# Arduino_Keyboard.net
KiCad netlist of a schematic drawn in EAGLE
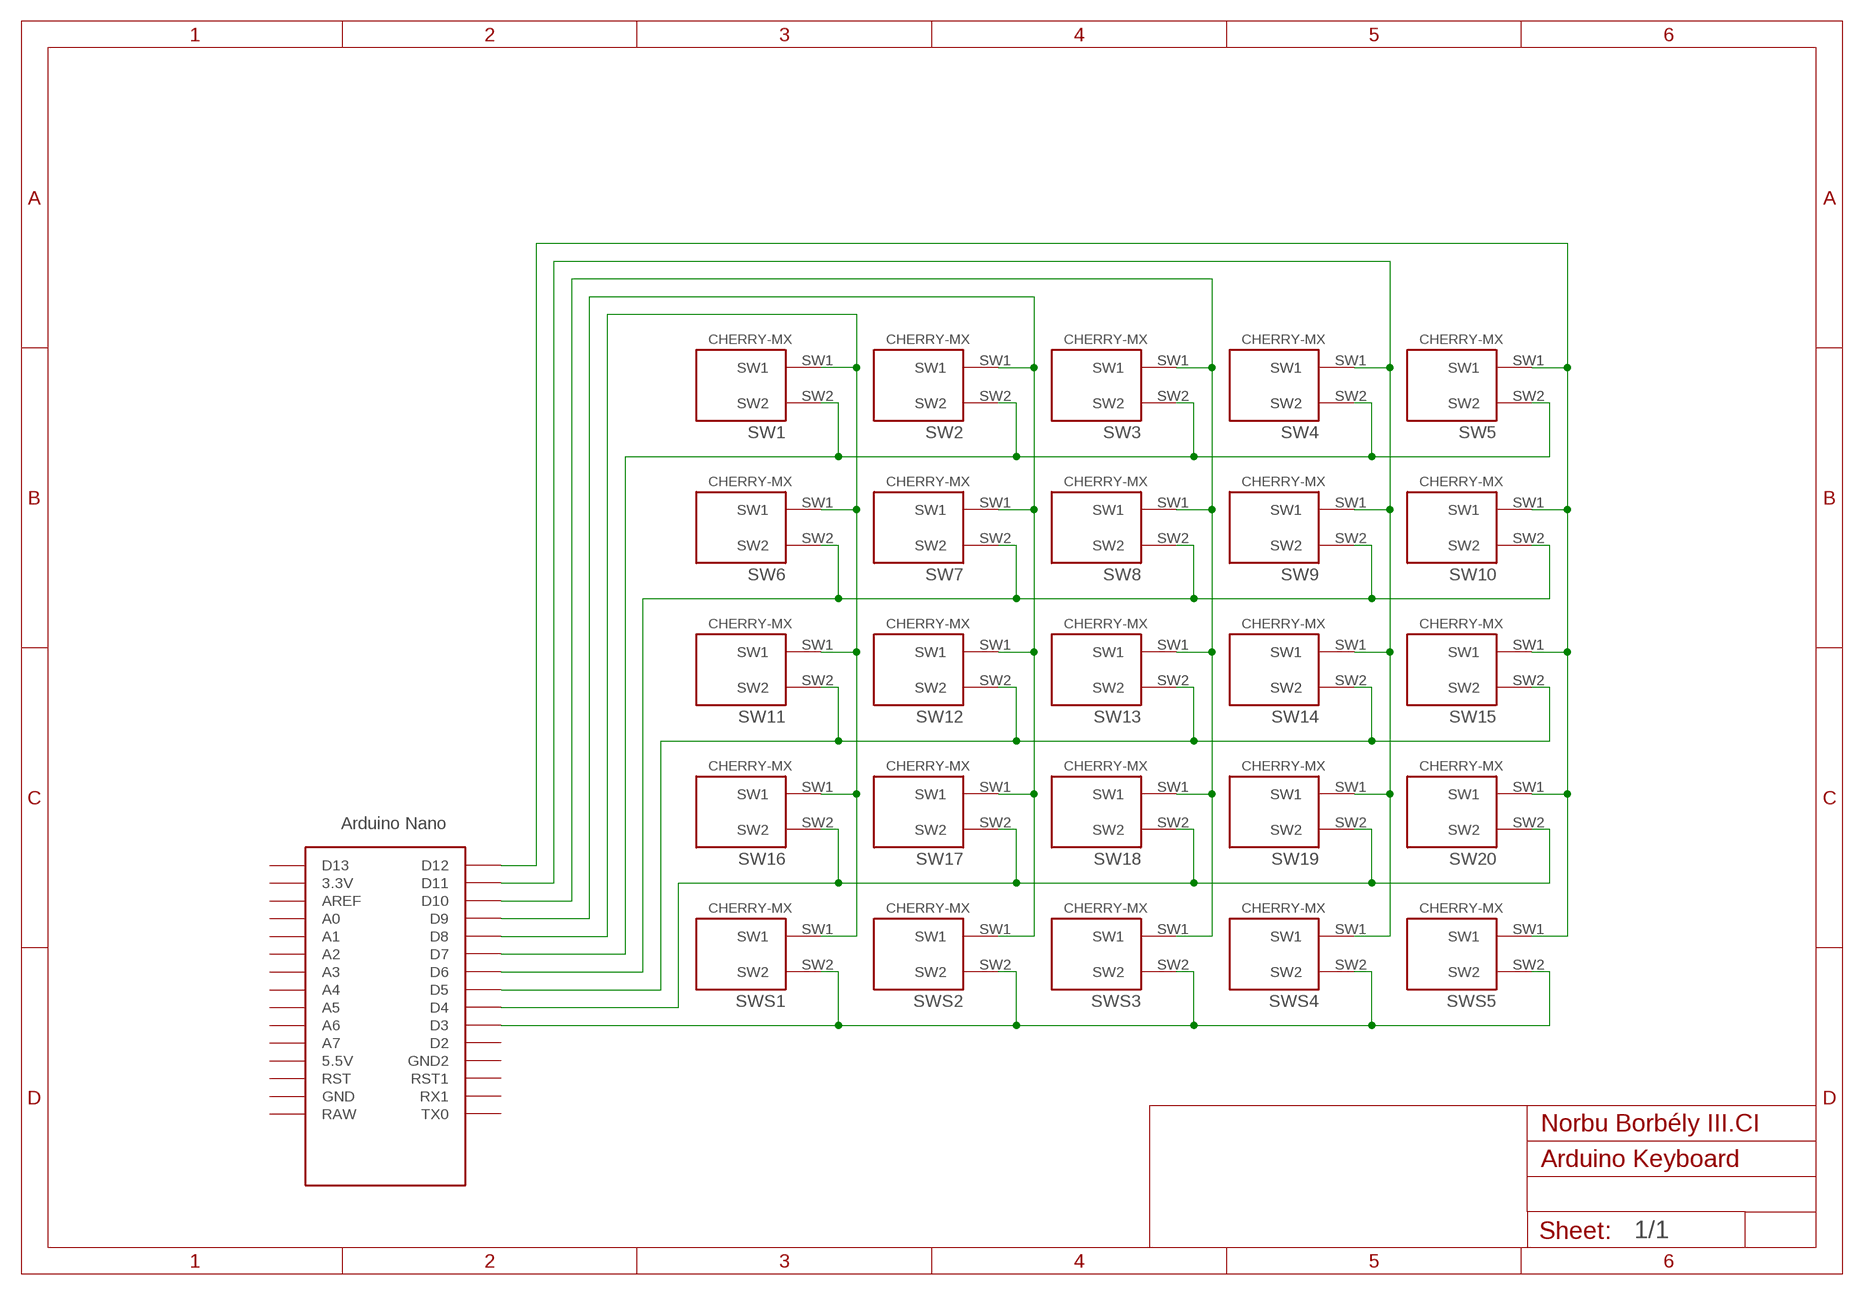
[diagram p0: schematic, sheet 1]

(export (version "E")
  (design (tool "Eeschema 10.0.6"))
  (components
    (comp (ref "SW1")
      (value "CHERRY-MXSTANDARD")
      (footprint "eagle-import:CHERRY-MX")
      (libsource (lib "eagle-import") (part "CHERRY-MXSTANDARD"))
    )
    (comp (ref "SW2")
      (value "CHERRY-MXSTANDARD")
      (footprint "eagle-import:CHERRY-MX")
      (libsource (lib "eagle-import") (part "CHERRY-MXSTANDARD"))
    )
    (comp (ref "SW3")
      (value "CHERRY-MXSTANDARD")
      (footprint "eagle-import:CHERRY-MX")
      (libsource (lib "eagle-import") (part "CHERRY-MXSTANDARD"))
    )
    (comp (ref "SW4")
      (value "CHERRY-MXSTANDARD")
      (footprint "eagle-import:CHERRY-MX")
      (libsource (lib "eagle-import") (part "CHERRY-MXSTANDARD"))
    )
    (comp (ref "SW5")
      (value "CHERRY-MXSTANDARD")
      (footprint "eagle-import:CHERRY-MX")
      (libsource (lib "eagle-import") (part "CHERRY-MXSTANDARD"))
    )
    (comp (ref "SW6")
      (value "CHERRY-MXSTANDARD")
      (footprint "eagle-import:CHERRY-MX")
      (libsource (lib "eagle-import") (part "CHERRY-MXSTANDARD"))
    )
    (comp (ref "SW7")
      (value "CHERRY-MXSTANDARD")
      (footprint "eagle-import:CHERRY-MX")
      (libsource (lib "eagle-import") (part "CHERRY-MXSTANDARD"))
    )
    (comp (ref "SW8")
      (value "CHERRY-MXSTANDARD")
      (footprint "eagle-import:CHERRY-MX")
      (libsource (lib "eagle-import") (part "CHERRY-MXSTANDARD"))
    )
    (comp (ref "SW9")
      (value "CHERRY-MXSTANDARD")
      (footprint "eagle-import:CHERRY-MX")
      (libsource (lib "eagle-import") (part "CHERRY-MXSTANDARD"))
    )
    (comp (ref "SW10")
      (value "CHERRY-MXSTANDARD")
      (footprint "eagle-import:CHERRY-MX")
      (libsource (lib "eagle-import") (part "CHERRY-MXSTANDARD"))
    )
    (comp (ref "SW11")
      (value "CHERRY-MXSTANDARD")
      (footprint "eagle-import:CHERRY-MX")
      (libsource (lib "eagle-import") (part "CHERRY-MXSTANDARD"))
    )
    (comp (ref "SW12")
      (value "CHERRY-MXSTANDARD")
      (footprint "eagle-import:CHERRY-MX")
      (libsource (lib "eagle-import") (part "CHERRY-MXSTANDARD"))
    )
    (comp (ref "SW13")
      (value "CHERRY-MXSTANDARD")
      (footprint "eagle-import:CHERRY-MX")
      (libsource (lib "eagle-import") (part "CHERRY-MXSTANDARD"))
    )
    (comp (ref "SW14")
      (value "CHERRY-MXSTANDARD")
      (footprint "eagle-import:CHERRY-MX")
      (libsource (lib "eagle-import") (part "CHERRY-MXSTANDARD"))
    )
    (comp (ref "SW15")
      (value "CHERRY-MXSTANDARD")
      (footprint "eagle-import:CHERRY-MX")
      (libsource (lib "eagle-import") (part "CHERRY-MXSTANDARD"))
    )
    (comp (ref "SW16")
      (value "CHERRY-MXSTANDARD")
      (footprint "eagle-import:CHERRY-MX")
      (libsource (lib "eagle-import") (part "CHERRY-MXSTANDARD"))
    )
    (comp (ref "SW17")
      (value "CHERRY-MXSTANDARD")
      (footprint "eagle-import:CHERRY-MX")
      (libsource (lib "eagle-import") (part "CHERRY-MXSTANDARD"))
    )
    (comp (ref "SW18")
      (value "CHERRY-MXSTANDARD")
      (footprint "eagle-import:CHERRY-MX")
      (libsource (lib "eagle-import") (part "CHERRY-MXSTANDARD"))
    )
    (comp (ref "SW19")
      (value "CHERRY-MXSTANDARD")
      (footprint "eagle-import:CHERRY-MX")
      (libsource (lib "eagle-import") (part "CHERRY-MXSTANDARD"))
    )
    (comp (ref "SW20")
      (value "CHERRY-MXSTANDARD")
      (footprint "eagle-import:CHERRY-MX")
      (libsource (lib "eagle-import") (part "CHERRY-MXSTANDARD"))
    )
    (comp (ref "SWS1")
      (value "CHERRY-MXSTANDARD")
      (footprint "eagle-import:CHERRY-MX")
      (libsource (lib "eagle-import") (part "CHERRY-MXSTANDARD"))
    )
    (comp (ref "SWS2")
      (value "CHERRY-MXSTANDARD")
      (footprint "eagle-import:CHERRY-MX")
      (libsource (lib "eagle-import") (part "CHERRY-MXSTANDARD"))
    )
    (comp (ref "SWS3")
      (value "CHERRY-MXSTANDARD")
      (footprint "eagle-import:CHERRY-MX")
      (libsource (lib "eagle-import") (part "CHERRY-MXSTANDARD"))
    )
    (comp (ref "SWS4")
      (value "CHERRY-MXSTANDARD")
      (footprint "eagle-import:CHERRY-MX")
      (libsource (lib "eagle-import") (part "CHERRY-MXSTANDARD"))
    )
    (comp (ref "SWS5")
      (value "CHERRY-MXSTANDARD")
      (footprint "eagle-import:CHERRY-MX")
      (libsource (lib "eagle-import") (part "CHERRY-MXSTANDARD"))
    )
    (comp (ref "U$1")
      (value "NANO")
      (footprint "eagle-import:NANO")
      (libsource (lib "eagle-import") (part "NANO"))
    )
  )
  (nets
    (net (code "1") (name "Net-(SW1-PadSW1)") (class "Default")
      (node (ref "SW1") (pin "SW1") (pinfunction "SW1_SW1") (pintype "bidirectional"))
      (node (ref "SW11") (pin "SW1") (pinfunction "SW1_SW1") (pintype "bidirectional"))
      (node (ref "SW16") (pin "SW1") (pinfunction "SW1_SW1") (pintype "bidirectional"))
      (node (ref "SW6") (pin "SW1") (pinfunction "SW1_SW1") (pintype "bidirectional"))
      (node (ref "SWS1") (pin "SW1") (pinfunction "SW1_SW1") (pintype "bidirectional"))
      (node (ref "U$1") (pin "D8") (pinfunction "D8_D8") (pintype "bidirectional"))
    )
    (net (code "2") (name "Net-(SW1-PadSW2)") (class "Default")
      (node (ref "SW1") (pin "SW2") (pinfunction "SW2_SW2") (pintype "bidirectional"))
      (node (ref "SW2") (pin "SW2") (pinfunction "SW2_SW2") (pintype "bidirectional"))
      (node (ref "SW3") (pin "SW2") (pinfunction "SW2_SW2") (pintype "bidirectional"))
      (node (ref "SW4") (pin "SW2") (pinfunction "SW2_SW2") (pintype "bidirectional"))
      (node (ref "SW5") (pin "SW2") (pinfunction "SW2_SW2") (pintype "bidirectional"))
      (node (ref "U$1") (pin "D7") (pinfunction "D7_D7") (pintype "bidirectional"))
    )
    (net (code "3") (name "Net-(SW10-PadSW1)") (class "Default")
      (node (ref "SW10") (pin "SW1") (pinfunction "SW1_SW1") (pintype "bidirectional"))
      (node (ref "SW15") (pin "SW1") (pinfunction "SW1_SW1") (pintype "bidirectional"))
      (node (ref "SW20") (pin "SW1") (pinfunction "SW1_SW1") (pintype "bidirectional"))
      (node (ref "SW5") (pin "SW1") (pinfunction "SW1_SW1") (pintype "bidirectional"))
      (node (ref "SWS5") (pin "SW1") (pinfunction "SW1_SW1") (pintype "bidirectional"))
      (node (ref "U$1") (pin "D12") (pinfunction "D12_D12") (pintype "bidirectional"))
    )
    (net (code "4") (name "Net-(SW10-PadSW2)") (class "Default")
      (node (ref "SW10") (pin "SW2") (pinfunction "SW2_SW2") (pintype "bidirectional"))
      (node (ref "SW6") (pin "SW2") (pinfunction "SW2_SW2") (pintype "bidirectional"))
      (node (ref "SW7") (pin "SW2") (pinfunction "SW2_SW2") (pintype "bidirectional"))
      (node (ref "SW8") (pin "SW2") (pinfunction "SW2_SW2") (pintype "bidirectional"))
      (node (ref "SW9") (pin "SW2") (pinfunction "SW2_SW2") (pintype "bidirectional"))
      (node (ref "U$1") (pin "D6") (pinfunction "D6_D6") (pintype "bidirectional"))
    )
    (net (code "5") (name "Net-(SW11-PadSW2)") (class "Default")
      (node (ref "SW11") (pin "SW2") (pinfunction "SW2_SW2") (pintype "bidirectional"))
      (node (ref "SW12") (pin "SW2") (pinfunction "SW2_SW2") (pintype "bidirectional"))
      (node (ref "SW13") (pin "SW2") (pinfunction "SW2_SW2") (pintype "bidirectional"))
      (node (ref "SW14") (pin "SW2") (pinfunction "SW2_SW2") (pintype "bidirectional"))
      (node (ref "SW15") (pin "SW2") (pinfunction "SW2_SW2") (pintype "bidirectional"))
      (node (ref "U$1") (pin "D5") (pinfunction "D5_D5") (pintype "bidirectional"))
    )
    (net (code "6") (name "Net-(SW12-PadSW1)") (class "Default")
      (node (ref "SW12") (pin "SW1") (pinfunction "SW1_SW1") (pintype "bidirectional"))
      (node (ref "SW17") (pin "SW1") (pinfunction "SW1_SW1") (pintype "bidirectional"))
      (node (ref "SW2") (pin "SW1") (pinfunction "SW1_SW1") (pintype "bidirectional"))
      (node (ref "SW7") (pin "SW1") (pinfunction "SW1_SW1") (pintype "bidirectional"))
      (node (ref "SWS2") (pin "SW1") (pinfunction "SW1_SW1") (pintype "bidirectional"))
      (node (ref "U$1") (pin "D9") (pinfunction "D9_D9") (pintype "bidirectional"))
    )
    (net (code "7") (name "Net-(SW13-PadSW1)") (class "Default")
      (node (ref "SW13") (pin "SW1") (pinfunction "SW1_SW1") (pintype "bidirectional"))
      (node (ref "SW18") (pin "SW1") (pinfunction "SW1_SW1") (pintype "bidirectional"))
      (node (ref "SW3") (pin "SW1") (pinfunction "SW1_SW1") (pintype "bidirectional"))
      (node (ref "SW8") (pin "SW1") (pinfunction "SW1_SW1") (pintype "bidirectional"))
      (node (ref "SWS3") (pin "SW1") (pinfunction "SW1_SW1") (pintype "bidirectional"))
      (node (ref "U$1") (pin "D10") (pinfunction "D10_D10") (pintype "bidirectional"))
    )
    (net (code "8") (name "Net-(SW14-PadSW1)") (class "Default")
      (node (ref "SW14") (pin "SW1") (pinfunction "SW1_SW1") (pintype "bidirectional"))
      (node (ref "SW19") (pin "SW1") (pinfunction "SW1_SW1") (pintype "bidirectional"))
      (node (ref "SW4") (pin "SW1") (pinfunction "SW1_SW1") (pintype "bidirectional"))
      (node (ref "SW9") (pin "SW1") (pinfunction "SW1_SW1") (pintype "bidirectional"))
      (node (ref "SWS4") (pin "SW1") (pinfunction "SW1_SW1") (pintype "bidirectional"))
      (node (ref "U$1") (pin "D11") (pinfunction "D11_D11") (pintype "bidirectional"))
    )
    (net (code "9") (name "Net-(SW16-PadSW2)") (class "Default")
      (node (ref "SW16") (pin "SW2") (pinfunction "SW2_SW2") (pintype "bidirectional"))
      (node (ref "SW17") (pin "SW2") (pinfunction "SW2_SW2") (pintype "bidirectional"))
      (node (ref "SW18") (pin "SW2") (pinfunction "SW2_SW2") (pintype "bidirectional"))
      (node (ref "SW19") (pin "SW2") (pinfunction "SW2_SW2") (pintype "bidirectional"))
      (node (ref "SW20") (pin "SW2") (pinfunction "SW2_SW2") (pintype "bidirectional"))
      (node (ref "U$1") (pin "D4") (pinfunction "D4_D4") (pintype "bidirectional"))
    )
    (net (code "10") (name "Net-(SWS1-PadSW2)") (class "Default")
      (node (ref "SWS1") (pin "SW2") (pinfunction "SW2_SW2") (pintype "bidirectional"))
      (node (ref "SWS2") (pin "SW2") (pinfunction "SW2_SW2") (pintype "bidirectional"))
      (node (ref "SWS3") (pin "SW2") (pinfunction "SW2_SW2") (pintype "bidirectional"))
      (node (ref "SWS4") (pin "SW2") (pinfunction "SW2_SW2") (pintype "bidirectional"))
      (node (ref "SWS5") (pin "SW2") (pinfunction "SW2_SW2") (pintype "bidirectional"))
      (node (ref "U$1") (pin "D3") (pinfunction "D3_D3") (pintype "bidirectional"))
    )
    (net (code "11") (name "unconnected-(U$1-5.5V-Pad5V)") (class "Default")
      (node (ref "U$1") (pin "5V") (pinfunction "5.5V_5V") (pintype "bidirectional"))
    )
    (net (code "12") (name "unconnected-(U$1-GND2-PadGND1)") (class "Default")
      (node (ref "U$1") (pin "GND1") (pinfunction "GND2_GND1") (pintype "bidirectional"))
    )
    (net (code "13") (name "unconnected-(U$1-Pad3.3V)") (class "Default")
      (node (ref "U$1") (pin "3.3V") (pinfunction "3.3V_3.3V") (pintype "bidirectional"))
    )
    (net (code "14") (name "unconnected-(U$1-PadA0)") (class "Default")
      (node (ref "U$1") (pin "A0") (pinfunction "A0_A0") (pintype "bidirectional"))
    )
    (net (code "15") (name "unconnected-(U$1-PadA1)") (class "Default")
      (node (ref "U$1") (pin "A1") (pinfunction "A1_A1") (pintype "bidirectional"))
    )
    (net (code "16") (name "unconnected-(U$1-PadA2)") (class "Default")
      (node (ref "U$1") (pin "A2") (pinfunction "A2_A2") (pintype "bidirectional"))
    )
    (net (code "17") (name "unconnected-(U$1-PadA3)") (class "Default")
      (node (ref "U$1") (pin "A3") (pinfunction "A3_A3") (pintype "bidirectional"))
    )
    (net (code "18") (name "unconnected-(U$1-PadA4)") (class "Default")
      (node (ref "U$1") (pin "A4") (pinfunction "A4_A4") (pintype "bidirectional"))
    )
    (net (code "19") (name "unconnected-(U$1-PadA5)") (class "Default")
      (node (ref "U$1") (pin "A5") (pinfunction "A5_A5") (pintype "bidirectional"))
    )
    (net (code "20") (name "unconnected-(U$1-PadA6)") (class "Default")
      (node (ref "U$1") (pin "A6") (pinfunction "A6_A6") (pintype "bidirectional"))
    )
    (net (code "21") (name "unconnected-(U$1-PadA7)") (class "Default")
      (node (ref "U$1") (pin "A7") (pinfunction "A7_A7") (pintype "bidirectional"))
    )
    (net (code "22") (name "unconnected-(U$1-PadAREF)") (class "Default")
      (node (ref "U$1") (pin "AREF") (pinfunction "AREF_AREF") (pintype "bidirectional"))
    )
    (net (code "23") (name "unconnected-(U$1-PadD2)") (class "Default")
      (node (ref "U$1") (pin "D2") (pinfunction "D2_D2") (pintype "bidirectional"))
    )
    (net (code "24") (name "unconnected-(U$1-PadD13)") (class "Default")
      (node (ref "U$1") (pin "D13") (pinfunction "D13_D13") (pintype "bidirectional"))
    )
    (net (code "25") (name "unconnected-(U$1-PadGND)") (class "Default")
      (node (ref "U$1") (pin "GND") (pinfunction "GND_GND") (pintype "bidirectional"))
    )
    (net (code "26") (name "unconnected-(U$1-PadRAW)") (class "Default")
      (node (ref "U$1") (pin "RAW") (pinfunction "RAW_RAW") (pintype "bidirectional"))
    )
    (net (code "27") (name "unconnected-(U$1-PadRST)") (class "Default")
      (node (ref "U$1") (pin "RST") (pinfunction "RST_RST") (pintype "bidirectional"))
    )
    (net (code "28") (name "unconnected-(U$1-PadRST1)") (class "Default")
      (node (ref "U$1") (pin "RST1") (pinfunction "RST1_RST1") (pintype "bidirectional"))
    )
    (net (code "29") (name "unconnected-(U$1-PadRX1)") (class "Default")
      (node (ref "U$1") (pin "RX1") (pinfunction "RX1_RX1") (pintype "bidirectional"))
    )
    (net (code "30") (name "unconnected-(U$1-PadTX0)") (class "Default")
      (node (ref "U$1") (pin "TX0") (pinfunction "TX0_TX0") (pintype "bidirectional"))
    )
  )
)
